# M8-Level.net
KiCad netlist of a schematic drawn in EAGLE
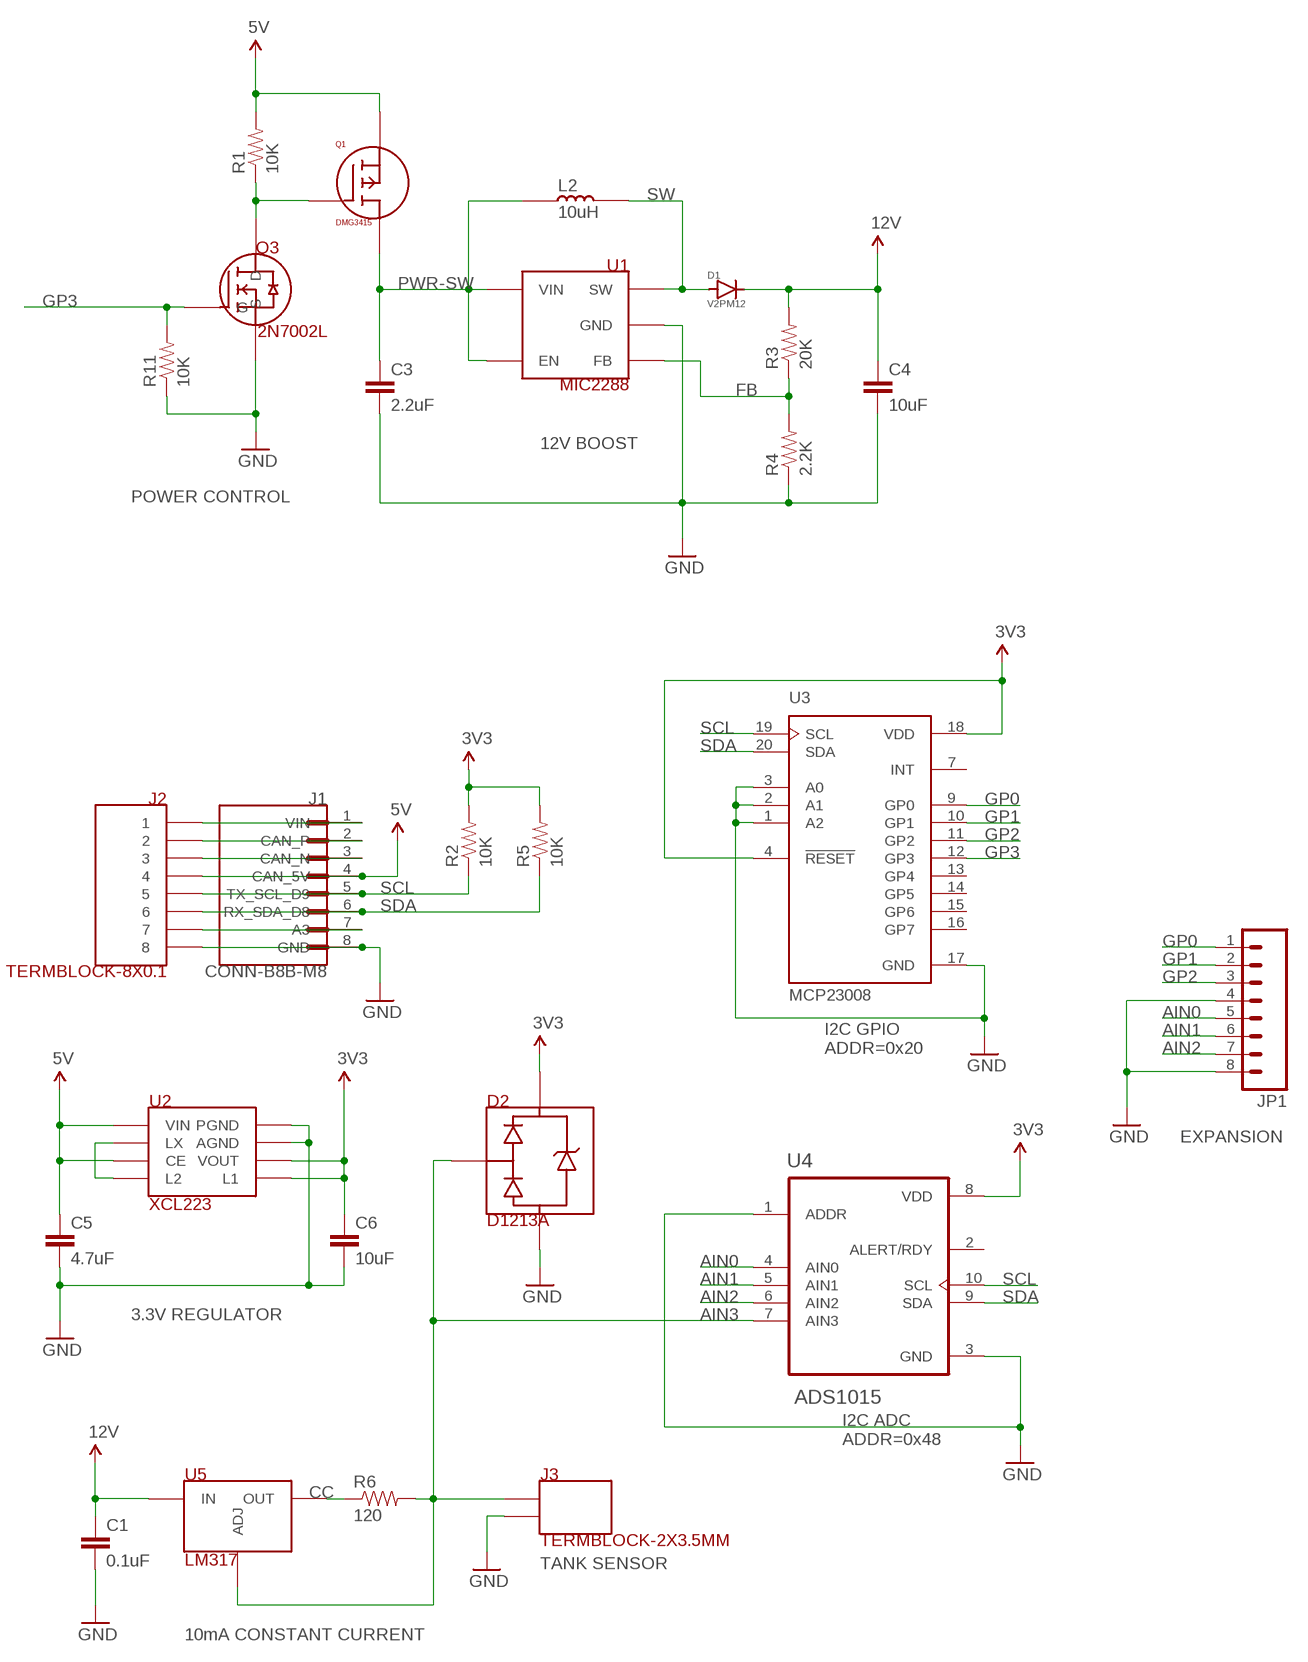
[diagram p0: schematic, sheet 1]

(export (version "E")
  (design (tool "Eeschema 10.0.6"))
  (components
    (comp (ref "C1")
      (value "0.1uF")
      (footprint "eagle-import:0603-CAP")
      (libsource (lib "eagle-import") (part "CAP-0.1UF-0603"))
    )
    (comp (ref "C3")
      (value "2.2uF")
      (footprint "eagle-import:0603-CAP")
      (libsource (lib "eagle-import") (part "CAP-2.2UF-0603"))
    )
    (comp (ref "C4")
      (value "10uF")
      (footprint "eagle-import:0603-CAP")
      (libsource (lib "eagle-import") (part "CAP-10UF-0603"))
    )
    (comp (ref "C5")
      (value "4.7uF")
      (footprint "eagle-import:0603-CAP")
      (libsource (lib "eagle-import") (part "CAP-4.7UF-0603"))
    )
    (comp (ref "C6")
      (value "10uF")
      (footprint "eagle-import:0603-CAP")
      (libsource (lib "eagle-import") (part "CAP-10UF-0603"))
    )
    (comp (ref "D1")
      (value "V2PM12")
      (footprint "eagle-import:DO-219AD-VISHAY")
      (libsource (lib "eagle-import") (part "V2PM12-SHOTTKY-DIODE"))
    )
    (comp (ref "D2")
      (value "D1213A")
      (footprint "eagle-import:DLP")
      (libsource (lib "eagle-import") (part "D1213A-DLP"))
    )
    (comp (ref "J1")
      (value "CONN-B8B-M8")
      (footprint "eagle-import:JST_B8B-PH-SM4-TB(LF)(SN)")
      (libsource (lib "eagle-import") (part "CONN-B8B-M8"))
    )
    (comp (ref "J2")
      (value "TERMBLOCK-8X0.1")
      (footprint "eagle-import:TERMBLOCK-8X0.1")
      (libsource (lib "eagle-import") (part "TERMBLOCK-8X0.1"))
    )
    (comp (ref "J3")
      (value "TERMBLOCK-2X3.5MM")
      (footprint "eagle-import:TERMBLOCK-2X3.5MM")
      (libsource (lib "eagle-import") (part "TERMBLOCK-2X3.5MM"))
    )
    (comp (ref "JP1")
      (value "M08SILK_FEMALE_PTH")
      (footprint "eagle-import:1X08")
      (libsource (lib "eagle-import") (part "M08SILK_FEMALE_PTH"))
    )
    (comp (ref "L2")
      (value "10uH")
      (footprint "eagle-import:BOURNS-INDUCTOR-3X3")
      (libsource (lib "eagle-import") (part "INDUCTOR-10UH"))
    )
    (comp (ref "Q1")
      (value "DMG3415")
      (footprint "eagle-import:2N7002L")
      (libsource (lib "eagle-import") (part "BS250-P-MOSFET"))
    )
    (comp (ref "Q3")
      (value "2N7002L")
      (footprint "eagle-import:2N7002L")
      (libsource (lib "eagle-import") (part "2N7002L"))
    )
    (comp (ref "R1")
      (value "10K")
      (footprint "eagle-import:0603-RES")
      (libsource (lib "eagle-import") (part "RES-10K-06030603"))
    )
    (comp (ref "R2")
      (value "10K")
      (footprint "eagle-import:0603-RES")
      (libsource (lib "eagle-import") (part "RES-10K-06030603"))
    )
    (comp (ref "R3")
      (value "20K")
      (footprint "eagle-import:0603-RES")
      (libsource (lib "eagle-import") (part "RES-20K-06030603"))
    )
    (comp (ref "R4")
      (value "2.2K")
      (footprint "eagle-import:0603-RES")
      (libsource (lib "eagle-import") (part "RES-2.2K-06030603"))
    )
    (comp (ref "R5")
      (value "10K")
      (footprint "eagle-import:0603-RES")
      (libsource (lib "eagle-import") (part "RES-10K-06030603"))
    )
    (comp (ref "R6")
      (value "120")
      (footprint "eagle-import:0603-RES")
      (libsource (lib "eagle-import") (part "RES-120-0603"))
    )
    (comp (ref "R11")
      (value "10K")
      (footprint "eagle-import:0603-RES")
      (libsource (lib "eagle-import") (part "RES-10K-06030603"))
    )
    (comp (ref "U1")
      (value "MIC2288")
      (footprint "eagle-import:TSOT23-5-MICROCHIP")
      (libsource (lib "eagle-import") (part "MIC2288"))
    )
    (comp (ref "U2")
      (value "XCL223")
      (footprint "eagle-import:REG-XCL223-LESS-CREAM")
      (libsource (lib "eagle-import") (part "REG-XCL223"))
    )
    (comp (ref "U3")
      (value "MCP23008")
      (footprint "eagle-import:QFN21P50_400X400X100L40X24T270N")
      (fields (field (name "MF") "Microchip Technology") (field (name "MP") "MCP23008T-E/ML"))
      (libsource (lib "eagle-import") (part "MCP23008T-E/ML"))
    )
    (comp (ref "U4")
      (value "ADS1015")
      (footprint "eagle-import:SOP50P490X110-10N")
      (fields
        (field (name "DIGI-KEY_PART_NUMBER") "296-41185-1-ND")
        (field (name "MF") "Texas Instruments")
        (field (name "MP") "ADS1015IDGSR")
      )
      (libsource (lib "eagle-import") (part "ADS1015IDGSR"))
    )
    (comp (ref "U5")
      (value "LM317")
      (footprint "eagle-import:8-SOIC-ON751")
      (libsource (lib "eagle-import") (part "LM317"))
    )
  )
  (nets
    (net (code "1") (name "/AIN0") (class "Default")
      (node (ref "JP1") (pin "5") (pinfunction "5_5") (pintype "passive"))
      (node (ref "U4") (pin "4") (pinfunction "AIN0_4") (pintype "input"))
    )
    (net (code "2") (name "/AIN1") (class "Default")
      (node (ref "JP1") (pin "6") (pinfunction "6_6") (pintype "passive"))
      (node (ref "U4") (pin "5") (pinfunction "AIN1_5") (pintype "input"))
    )
    (net (code "3") (name "/AIN2") (class "Default")
      (node (ref "JP1") (pin "7") (pinfunction "7_7") (pintype "passive"))
      (node (ref "U4") (pin "6") (pinfunction "AIN2_6") (pintype "input"))
    )
    (net (code "4") (name "/AIN3") (class "Default")
      (node (ref "D2") (pin "SIGNAL") (pinfunction "SIGNAL_SIGNAL") (pintype "bidirectional"))
      (node (ref "J3") (pin "1") (pinfunction "1_1") (pintype "passive"))
      (node (ref "R6") (pin "2") (pinfunction "2_2") (pintype "passive"))
      (node (ref "U4") (pin "7") (pinfunction "AIN3_7") (pintype "input"))
      (node (ref "U5") (pin "4") (pinfunction "ADJ_4") (pintype "passive"))
    )
    (net (code "5") (name "/CC") (class "Default")
      (node (ref "R6") (pin "1") (pinfunction "1_1") (pintype "passive"))
      (node (ref "U5") (pin "2") (pinfunction "OUT_2") (pintype "passive"))
      (node (ref "U5") (pin "3") (pinfunction "OUT_3") (pintype "passive"))
      (node (ref "U5") (pin "6") (pinfunction "OUT_6") (pintype "passive"))
      (node (ref "U5") (pin "7") (pinfunction "OUT_7") (pintype "passive"))
    )
    (net (code "6") (name "/FB") (class "Default")
      (node (ref "R3") (pin "1") (pinfunction "1_1") (pintype "passive"))
      (node (ref "R4") (pin "2") (pinfunction "2_2") (pintype "passive"))
      (node (ref "U1") (pin "3") (pinfunction "FB_3") (pintype "input"))
    )
    (net (code "7") (name "/GP0") (class "Default")
      (node (ref "JP1") (pin "1") (pinfunction "1_1") (pintype "passive"))
      (node (ref "U3") (pin "9") (pinfunction "GP0_9") (pintype "bidirectional"))
    )
    (net (code "8") (name "/GP1") (class "Default")
      (node (ref "JP1") (pin "2") (pinfunction "2_2") (pintype "passive"))
      (node (ref "U3") (pin "10") (pinfunction "GP1_10") (pintype "bidirectional"))
    )
    (net (code "9") (name "/GP2") (class "Default")
      (node (ref "JP1") (pin "3") (pinfunction "3_3") (pintype "passive"))
      (node (ref "U3") (pin "11") (pinfunction "GP2_11") (pintype "bidirectional"))
    )
    (net (code "10") (name "/GP3") (class "Default")
      (node (ref "Q3") (pin "1") (pinfunction "G_1") (pintype "bidirectional"))
      (node (ref "R11") (pin "2") (pinfunction "2_2") (pintype "passive"))
      (node (ref "U3") (pin "12") (pinfunction "GP3_12") (pintype "bidirectional"))
    )
    (net (code "11") (name "/PWR-SW") (class "Default")
      (node (ref "C3") (pin "1") (pinfunction "1_1") (pintype "passive"))
      (node (ref "L2") (pin "1") (pinfunction "P$1_1") (pintype "passive"))
      (node (ref "Q1") (pin "3") (pinfunction "D_3") (pintype "bidirectional"))
      (node (ref "U1") (pin "4") (pinfunction "EN_4") (pintype "input"))
      (node (ref "U1") (pin "5") (pinfunction "VIN_5") (pintype "power_in"))
    )
    (net (code "12") (name "/SCL") (class "Default")
      (node (ref "J1") (pin "5") (pinfunction "TX_SCL_D9_5") (pintype "passive"))
      (node (ref "J2") (pin "P$5") (pinfunction "5_P$5") (pintype "passive"))
      (node (ref "R2") (pin "1") (pinfunction "1_1") (pintype "passive"))
      (node (ref "U3") (pin "19") (pinfunction "SCL_19") (pintype "input"))
      (node (ref "U4") (pin "10") (pinfunction "SCL_10") (pintype "input"))
    )
    (net (code "13") (name "/SDA") (class "Default")
      (node (ref "J1") (pin "6") (pinfunction "RX_SDA_D8_6") (pintype "passive"))
      (node (ref "J2") (pin "P$6") (pinfunction "6_P$6") (pintype "passive"))
      (node (ref "R5") (pin "1") (pinfunction "1_1") (pintype "passive"))
      (node (ref "U3") (pin "20") (pinfunction "SDA_20") (pintype "bidirectional"))
      (node (ref "U4") (pin "9") (pinfunction "SDA_9") (pintype "bidirectional"))
    )
    (net (code "14") (name "/SW") (class "Default")
      (node (ref "D1") (pin "A") (pinfunction "ANODE_A") (pintype "bidirectional"))
      (node (ref "L2") (pin "2") (pinfunction "P$2_2") (pintype "passive"))
      (node (ref "U1") (pin "1") (pinfunction "SW_1") (pintype "output"))
    )
    (net (code "15") (name "3V3") (class "Default")
      (node (ref "C6") (pin "1") (pinfunction "1_1") (pintype "passive"))
      (node (ref "D2") (pin "VCC") (pinfunction "VCC_VCC") (pintype "power_in"))
      (node (ref "R2") (pin "2") (pinfunction "2_2") (pintype "passive"))
      (node (ref "R5") (pin "2") (pinfunction "2_2") (pintype "passive"))
      (node (ref "U2") (pin "3") (pinfunction "VOUT_3") (pintype "passive"))
      (node (ref "U2") (pin "7") (pinfunction "L1_7") (pintype "passive"))
      (node (ref "U3") (pin "18") (pinfunction "VDD_18") (pintype "power_in"))
      (node (ref "U3") (pin "4") (pinfunction "~{RESET}_4") (pintype "input"))
      (node (ref "U4") (pin "8") (pinfunction "VDD_8") (pintype "power_in"))
    )
    (net (code "16") (name "5V") (class "Default")
      (node (ref "C5") (pin "1") (pinfunction "1_1") (pintype "passive"))
      (node (ref "J1") (pin "4") (pinfunction "CAN_5V_4") (pintype "passive"))
      (node (ref "J2") (pin "P$4") (pinfunction "4_P$4") (pintype "passive"))
      (node (ref "Q1") (pin "2") (pinfunction "S_2") (pintype "bidirectional"))
      (node (ref "R1") (pin "2") (pinfunction "2_2") (pintype "passive"))
      (node (ref "U2") (pin "4") (pinfunction "CE_4") (pintype "input"))
      (node (ref "U2") (pin "6") (pinfunction "VIN_6") (pintype "power_in"))
    )
    (net (code "17") (name "12V") (class "Default")
      (node (ref "C1") (pin "1") (pinfunction "1_1") (pintype "passive"))
      (node (ref "C4") (pin "1") (pinfunction "1_1") (pintype "passive"))
      (node (ref "D1") (pin "C") (pinfunction "CATHODE_C") (pintype "bidirectional"))
      (node (ref "R3") (pin "2") (pinfunction "2_2") (pintype "passive"))
      (node (ref "U5") (pin "1") (pinfunction "IN_1") (pintype "passive"))
    )
    (net (code "18") (name "GND") (class "Default")
      (node (ref "C1") (pin "2") (pinfunction "2_2") (pintype "passive"))
      (node (ref "C3") (pin "2") (pinfunction "2_2") (pintype "passive"))
      (node (ref "C4") (pin "2") (pinfunction "2_2") (pintype "passive"))
      (node (ref "C5") (pin "2") (pinfunction "2_2") (pintype "passive"))
      (node (ref "C6") (pin "2") (pinfunction "2_2") (pintype "passive"))
      (node (ref "D2") (pin "GND") (pinfunction "GND_GND") (pintype "power_in"))
      (node (ref "J1") (pin "8") (pinfunction "GND_8") (pintype "passive"))
      (node (ref "J2") (pin "P$8") (pinfunction "8_P$8") (pintype "passive"))
      (node (ref "J3") (pin "2") (pinfunction "2_2") (pintype "passive"))
      (node (ref "JP1") (pin "4") (pinfunction "4_4") (pintype "passive"))
      (node (ref "JP1") (pin "8") (pinfunction "8_8") (pintype "passive"))
      (node (ref "Q3") (pin "2") (pinfunction "S_2") (pintype "bidirectional"))
      (node (ref "R11") (pin "1") (pinfunction "1_1") (pintype "passive"))
      (node (ref "R4") (pin "1") (pinfunction "1_1") (pintype "passive"))
      (node (ref "U1") (pin "2") (pinfunction "GND_2") (pintype "passive"))
      (node (ref "U2") (pin "1") (pinfunction "PGND_1") (pintype "passive"))
      (node (ref "U2") (pin "2") (pinfunction "AGND_2") (pintype "passive"))
      (node (ref "U3") (pin "1") (pinfunction "A2_1") (pintype "bidirectional"))
      (node (ref "U3") (pin "17") (pinfunction "GND_17") (pintype "power_in"))
      (node (ref "U3") (pin "2") (pinfunction "A1_2") (pintype "input"))
      (node (ref "U3") (pin "3") (pinfunction "A0_3") (pintype "input"))
      (node (ref "U4") (pin "1") (pinfunction "ADDR_1") (pintype "input"))
      (node (ref "U4") (pin "3") (pinfunction "GND_3") (pintype "power_in"))
    )
    (net (code "19") (name "Net-(J1-A3)") (class "Default")
      (node (ref "J1") (pin "7") (pinfunction "A3_7") (pintype "passive"))
      (node (ref "J2") (pin "P$7") (pinfunction "7_P$7") (pintype "passive"))
    )
    (net (code "20") (name "Net-(J1-CAN_N)") (class "Default")
      (node (ref "J1") (pin "3") (pinfunction "CAN_N_3") (pintype "passive"))
      (node (ref "J2") (pin "P$3") (pinfunction "3_P$3") (pintype "passive"))
    )
    (net (code "21") (name "Net-(J1-CAN_P)") (class "Default")
      (node (ref "J1") (pin "2") (pinfunction "CAN_P_2") (pintype "passive"))
      (node (ref "J2") (pin "P$2") (pinfunction "2_P$2") (pintype "passive"))
    )
    (net (code "22") (name "Net-(J1-VIN)") (class "Default")
      (node (ref "J1") (pin "1") (pinfunction "VIN_1") (pintype "passive"))
      (node (ref "J2") (pin "P$1") (pinfunction "1_P$1") (pintype "passive"))
    )
    (net (code "23") (name "Net-(Q1-G)") (class "Default")
      (node (ref "Q1") (pin "1") (pinfunction "G_1") (pintype "bidirectional"))
      (node (ref "Q3") (pin "3") (pinfunction "D_3") (pintype "bidirectional"))
      (node (ref "R1") (pin "1") (pinfunction "1_1") (pintype "passive"))
    )
    (net (code "24") (name "Net-(U2-L2)") (class "Default")
      (node (ref "U2") (pin "5") (pinfunction "LX_5") (pintype "passive"))
      (node (ref "U2") (pin "8") (pinfunction "L2_8") (pintype "passive"))
    )
    (net (code "25") (name "unconnected-(U3-GP4-Pad13)") (class "Default")
      (node (ref "U3") (pin "13") (pinfunction "GP4_13") (pintype "bidirectional"))
    )
    (net (code "26") (name "unconnected-(U3-GP5-Pad14)") (class "Default")
      (node (ref "U3") (pin "14") (pinfunction "GP5_14") (pintype "bidirectional"))
    )
    (net (code "27") (name "unconnected-(U3-GP6-Pad15)") (class "Default")
      (node (ref "U3") (pin "15") (pinfunction "GP6_15") (pintype "bidirectional"))
    )
    (net (code "28") (name "unconnected-(U3-GP7-Pad16)") (class "Default")
      (node (ref "U3") (pin "16") (pinfunction "GP7_16") (pintype "bidirectional"))
    )
    (net (code "29") (name "unconnected-(U3-INT-Pad7)") (class "Default")
      (node (ref "U3") (pin "7") (pinfunction "INT_7") (pintype "output"))
    )
    (net (code "30") (name "unconnected-(U4-ALERT{slash}RDY-Pad2)") (class "Default")
      (node (ref "U4") (pin "2") (pinfunction "ALERT/RDY_2") (pintype "output"))
    )
  )
)
